# Debug.net
KiCad netlist of a schematic drawn in Altium Designer
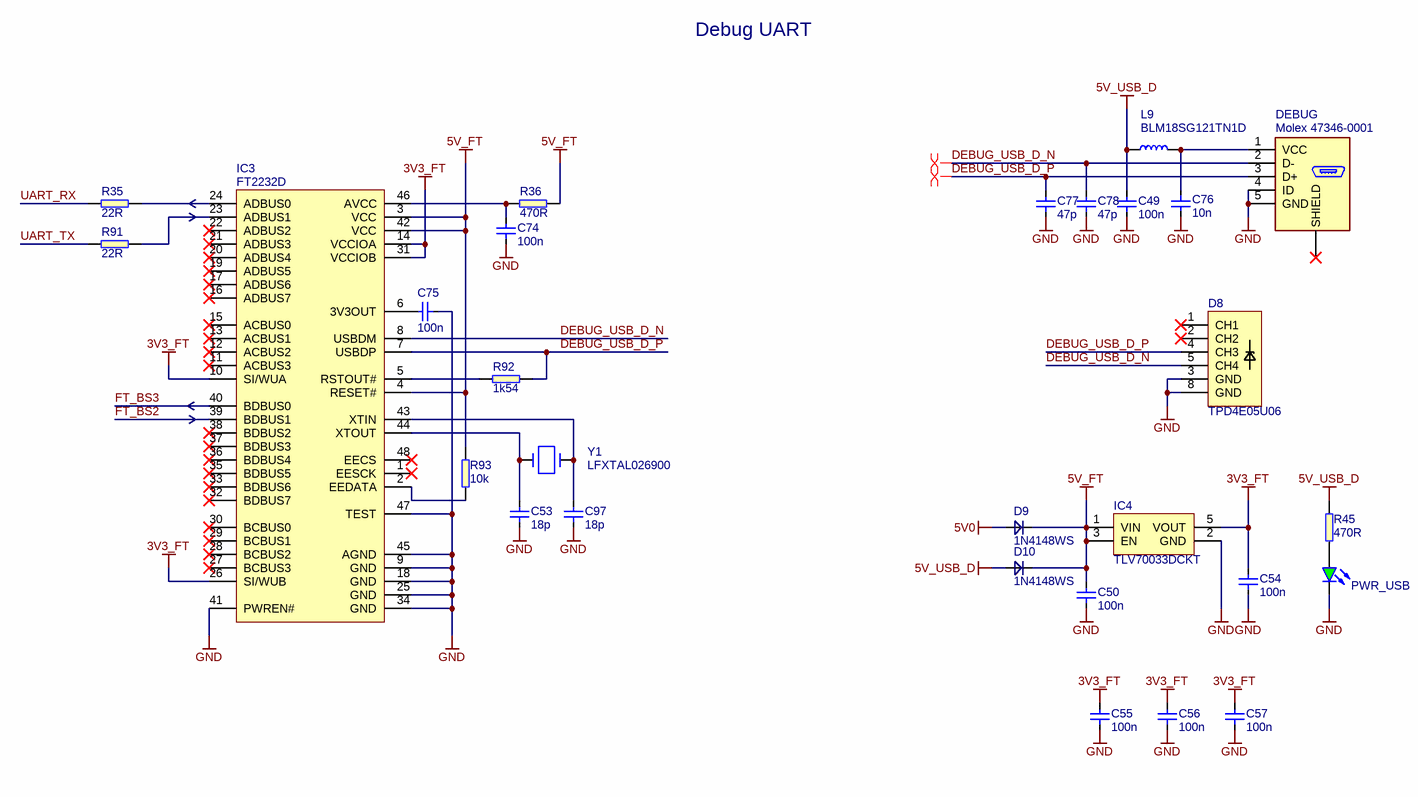
[diagram p0: Debug.SchDoc]

(export (version "E")
  (design (tool "Eeschema 10.0.6"))
  (components
    (comp (ref "C49")
      (value "100n")
      (footprint "0603")
      (description "MLCC SMT Capacitor 100nF 0603")
      (fields (field (name "PART NUMBER") "C_100n_0603") (field (name "MANUFACTURER") "WALSIN"))
      (libsource (lib "US-Plus-CPM") (part "C"))
    )
    (comp (ref "C50")
      (value "100n")
      (footprint "0402")
      (description "MLCC SMT Capacitor 100nF 0402")
      (fields (field (name "PART NUMBER") "C_100n_0402") (field (name "MANUFACTURER") "MULTICOMP"))
      (libsource (lib "US-Plus-CPM") (part "C"))
    )
    (comp (ref "C53")
      (value "18p")
      (footprint "0402")
      (description "MLCC SMT Capacitor 18pF 0603")
      (fields (field (name "PART NUMBER") "C_18p_0402") (field (name "MANUFACTURER") "KEMET"))
      (libsource (lib "US-Plus-CPM") (part "C"))
    )
    (comp (ref "C54")
      (value "100n")
      (footprint "0402")
      (description "MLCC SMT Capacitor 100nF 0402")
      (fields (field (name "PART NUMBER") "C_100n_0402") (field (name "MANUFACTURER") "MULTICOMP"))
      (libsource (lib "US-Plus-CPM") (part "C"))
    )
    (comp (ref "C55")
      (value "100n")
      (footprint "0402")
      (description "MLCC SMT Capacitor 100nF 0402")
      (fields (field (name "PART NUMBER") "C_100n_0402") (field (name "MANUFACTURER") "MULTICOMP"))
      (libsource (lib "US-Plus-CPM") (part "C"))
    )
    (comp (ref "C56")
      (value "100n")
      (footprint "0402")
      (description "MLCC SMT Capacitor 100nF 0402")
      (fields (field (name "PART NUMBER") "C_100n_0402") (field (name "MANUFACTURER") "MULTICOMP"))
      (libsource (lib "US-Plus-CPM") (part "C"))
    )
    (comp (ref "C57")
      (value "100n")
      (footprint "0402")
      (description "MLCC SMT Capacitor 100nF 0402")
      (fields (field (name "PART NUMBER") "C_100n_0402") (field (name "MANUFACTURER") "MULTICOMP"))
      (libsource (lib "US-Plus-CPM") (part "C"))
    )
    (comp (ref "C74")
      (value "100n")
      (footprint "0402")
      (description "MLCC SMT Capacitor 100nF 0402")
      (fields (field (name "PART NUMBER") "C_100n_0402") (field (name "MANUFACTURER") "MULTICOMP"))
      (libsource (lib "US-Plus-CPM") (part "C"))
    )
    (comp (ref "C75")
      (value "100n")
      (footprint "0402")
      (description "MLCC SMT Capacitor 100nF 0402")
      (fields (field (name "PART NUMBER") "C_100n_0402") (field (name "MANUFACTURER") "MULTICOMP"))
      (libsource (lib "US-Plus-CPM") (part "C"))
    )
    (comp (ref "C76")
      (value "10n")
      (footprint "0603")
      (description "MLCC SMT Capacitor 10nF 0603")
      (fields (field (name "PART NUMBER") "C_10n_0603") (field (name "MANUFACTURER") "AVX"))
      (libsource (lib "US-Plus-CPM") (part "C"))
    )
    (comp (ref "C77")
      (value "47p")
      (footprint "0402")
      (description "MLCC SMT Capacitor 47pF 0402")
      (fields (field (name "PART NUMBER") "C_47p_0402") (field (name "MANUFACTURER") "KEMET"))
      (libsource (lib "US-Plus-CPM") (part "C"))
    )
    (comp (ref "C78")
      (value "47p")
      (footprint "0402")
      (description "MLCC SMT Capacitor 47pF 0402")
      (fields (field (name "PART NUMBER") "C_47p_0402") (field (name "MANUFACTURER") "KEMET"))
      (libsource (lib "US-Plus-CPM") (part "C"))
    )
    (comp (ref "C97")
      (value "18p")
      (footprint "0402")
      (description "MLCC SMT Capacitor 18pF 0603")
      (fields (field (name "PART NUMBER") "C_18p_0402") (field (name "MANUFACTURER") "KEMET"))
      (libsource (lib "US-Plus-CPM") (part "C"))
    )
    (comp (ref "D8")
      (value "TPD4E05U06")
      (footprint "TPD4E05U06_PASS")
      (description "ESD Suppressors 4-CH")
      (fields
        (field (name "PART NUMBER") "TPD4E05U06_PASS")
        (field (name "MANUFACTURER") "Texas Instruments")
      )
      (libsource (lib "US-Plus-CPM") (part "TPD4E05U06"))
    )
    (comp (ref "D9")
      (value "1N4148WS")
      (footprint "SOD-323")
      (description "Diode small signal")
      (fields (field (name "MANUFACTURER") "MULTICOMP"))
      (libsource (lib "US-Plus-CPM") (part "diode"))
    )
    (comp (ref "D10")
      (value "1N4148WS")
      (footprint "SOD-323")
      (description "Diode small signal")
      (fields (field (name "MANUFACTURER") "MULTICOMP"))
      (libsource (lib "US-Plus-CPM") (part "diode"))
    )
    (comp (ref "DEBUG")
      (value "Molex 47346-0001")
      (footprint "CON-Molex-047346-0001")
      (description "USB - micro B Receptacle Connector 5 Position Surface Mount, Right Angle, Horizontal")
      (fields (field (name "PART NUMBER") "CON-Molex-47346-0001") (field (name "MANUFACTURER") "Molex"))
      (libsource (lib "US-Plus-CPM") (part "Micro USB B"))
    )
    (comp (ref "IC3")
      (value "FT2232D")
      (footprint "LQFP-48")
      (description "Dual USB-UART/FIFO")
      (fields (field (name "MANUFACTURER") "FTDI") (field (name "MPN") "FT2232D-REEL"))
      (libsource (lib "US-Plus-CPM") (part "FT2232"))
    )
    (comp (ref "IC4")
      (value "TLV70033DCKT")
      (footprint "SC70-5")
      (description "Voltage Regulator, 2V to 5.5V, 175mV Dropout, 3.3Vout, 200mAout")
      (fields (field (name "MANUFACTURER") "TEXAS INSTRUMENTS"))
      (libsource (lib "US-Plus-CPM") (part "TLV700"))
    )
    (comp (ref "L9")
      (value "BLM18SG121TN1D")
      (footprint "0603")
      (description "FERRITE BEAD, 0.025OHM, 3A, 0603")
      (fields (field (name "MANUFACTURER") "MURATA"))
      (libsource (lib "US-Plus-CPM") (part "Inductor SMT"))
    )
    (comp (ref "PWR_USB")
      (value "KPT-1608SGC")
      (footprint "LED0603")
      (description "LED Green 0603 case")
      (fields (field (name "PART NUMBER") "LED_G") (field (name "MANUFACTURER") "KINGBRIGHT"))
      (libsource (lib "US-Plus-CPM") (part "LED"))
    )
    (comp (ref "R35")
      (value "22R")
      (footprint "0402")
      (description "SMT Resistor 22R 0402")
      (fields (field (name "PART NUMBER") "R_22R_0402") (field (name "MANUFACTURER") "VISHAY"))
      (libsource (lib "") (part "R_1"))
    )
    (comp (ref "R36")
      (value "470R")
      (footprint "0402")
      (description "SMT Resistor 470R 0402")
      (fields (field (name "PART NUMBER") "R_470R_0402") (field (name "MANUFACTURER") "VISHAY"))
      (libsource (lib "US-Plus-CPM") (part "R"))
    )
    (comp (ref "R45")
      (value "470R")
      (footprint "0603")
      (description "SMT Resistor 470R 0603")
      (fields (field (name "PART NUMBER") "R_470R_0603") (field (name "MANUFACTURER") "BOURNS"))
      (libsource (lib "") (part "R_2"))
    )
    (comp (ref "R91")
      (value "22R")
      (footprint "0402")
      (description "SMT Resistor 22R 0402")
      (fields (field (name "PART NUMBER") "R_22R_0402") (field (name "MANUFACTURER") "VISHAY"))
      (libsource (lib "") (part "R_1"))
    )
    (comp (ref "R92")
      (value "1k54")
      (footprint "0402")
      (description "SMT Resistor 1k54 0402")
      (fields (field (name "PART NUMBER") "R_1k54_0402") (field (name "MANUFACTURER") "VISHAY"))
      (libsource (lib "US-Plus-CPM") (part "R"))
    )
    (comp (ref "R93")
      (value "10k")
      (footprint "0402")
      (description "SMT Resistor 0402")
      (fields (field (name "PART NUMBER") "R_10k_0402") (field (name "MANUFACTURER") "MULTICOMP"))
      (libsource (lib "") (part "R_1"))
    )
    (comp (ref "Y1")
      (value "LFXTAL026900")
      (footprint "crystal_smd")
      (description "CRYSTAL, 6MHZ, 18PF, SMD")
      (fields
        (field (name "PART NUMBER") "CRYSTAL_6MHz_SMD")
        (field (name "MANUFACTURER") "IQD FREQUENCY PRODUCTS")
      )
      (libsource (lib "US-Plus-CPM") (part "CRYSTAL"))
    )
  )
  (nets
    (net (code "1") (name "/DEBUG_USB_D_N") (class "Default")
      (node (ref "C78") (pin "2") (pinfunction "2_2") (pintype "passive"))
      (node (ref "D8") (pin "5") (pinfunction "CH4_5") (pintype "passive"))
      (node (ref "DEBUG") (pin "2") (pinfunction "D-_2") (pintype "passive"))
      (node (ref "IC3") (pin "8") (pinfunction "USBDM_8") (pintype "passive"))
    )
    (net (code "2") (name "/DEBUG_USB_D_P") (class "Default")
      (node (ref "C77") (pin "2") (pinfunction "2_2") (pintype "passive"))
      (node (ref "D8") (pin "4") (pinfunction "CH3_4") (pintype "passive"))
      (node (ref "DEBUG") (pin "3") (pinfunction "D+_3") (pintype "passive"))
      (node (ref "IC3") (pin "7") (pinfunction "USBDP_7") (pintype "passive"))
      (node (ref "R92") (pin "1") (pintype "passive"))
    )
    (net (code "3") (name "/FT_BS2") (class "Default")
      (node (ref "IC3") (pin "39") (pinfunction "BDBUS1_39") (pintype "passive"))
    )
    (net (code "4") (name "/FT_BS3") (class "Default")
      (node (ref "IC3") (pin "40") (pinfunction "BDBUS0_40") (pintype "passive"))
    )
    (net (code "5") (name "/UART_RX") (class "Default") (node (ref "R35") (pin "1") (pintype "passive")))
    (net (code "6") (name "/UART_TX") (class "Default") (node (ref "R91") (pin "1") (pintype "passive")))
    (net (code "7") (name "3V3_FT") (class "Default")
      (node (ref "C54") (pin "2") (pinfunction "2_2") (pintype "passive"))
      (node (ref "C55") (pin "2") (pinfunction "2_2") (pintype "passive"))
      (node (ref "C56") (pin "2") (pinfunction "2_2") (pintype "passive"))
      (node (ref "C57") (pin "2") (pinfunction "2_2") (pintype "passive"))
      (node (ref "IC3") (pin "10") (pinfunction "SI/WUA_10") (pintype "passive"))
      (node (ref "IC3") (pin "14") (pinfunction "VCCIOA_14") (pintype "passive"))
      (node (ref "IC3") (pin "26") (pinfunction "SI/WUB_26") (pintype "passive"))
      (node (ref "IC3") (pin "31") (pinfunction "VCCIOB_31") (pintype "passive"))
      (node (ref "IC4") (pin "5") (pinfunction "VOUT_5") (pintype "passive"))
    )
    (net (code "8") (name "5V0") (class "Default")
      (node (ref "D9") (pin "A") (pinfunction "A_A") (pintype "passive"))
    )
    (net (code "9") (name "5V_FT") (class "Default")
      (node (ref "C50") (pin "2") (pinfunction "2_2") (pintype "passive"))
      (node (ref "D10") (pin "C") (pinfunction "C_C") (pintype "passive"))
      (node (ref "D9") (pin "C") (pinfunction "C_C") (pintype "passive"))
      (node (ref "IC3") (pin "3") (pinfunction "VCC_3") (pintype "passive"))
      (node (ref "IC3") (pin "4") (pinfunction "RESET#_4") (pintype "passive"))
      (node (ref "IC3") (pin "42") (pinfunction "VCC_42") (pintype "passive"))
      (node (ref "IC4") (pin "1") (pinfunction "VIN_1") (pintype "passive"))
      (node (ref "IC4") (pin "3") (pinfunction "EN_3") (pintype "passive"))
      (node (ref "R36") (pin "1") (pintype "passive"))
      (node (ref "R93") (pin "2") (pintype "passive"))
    )
    (net (code "10") (name "5V_USB_D") (class "Default")
      (node (ref "C49") (pin "2") (pinfunction "2_2") (pintype "passive"))
      (node (ref "D10") (pin "A") (pinfunction "A_A") (pintype "passive"))
      (node (ref "L9") (pin "1") (pintype "passive"))
      (node (ref "R45") (pin "2") (pintype "passive"))
    )
    (net (code "11") (name "GND") (class "Default")
      (node (ref "C49") (pin "1") (pinfunction "1_1") (pintype "passive"))
      (node (ref "C50") (pin "1") (pinfunction "1_1") (pintype "passive"))
      (node (ref "C53") (pin "1") (pinfunction "1_1") (pintype "passive"))
      (node (ref "C54") (pin "1") (pinfunction "1_1") (pintype "passive"))
      (node (ref "C55") (pin "1") (pinfunction "1_1") (pintype "passive"))
      (node (ref "C56") (pin "1") (pinfunction "1_1") (pintype "passive"))
      (node (ref "C57") (pin "1") (pinfunction "1_1") (pintype "passive"))
      (node (ref "C74") (pin "1") (pinfunction "1_1") (pintype "passive"))
      (node (ref "C75") (pin "1") (pinfunction "1_1") (pintype "passive"))
      (node (ref "C76") (pin "2") (pinfunction "2_2") (pintype "passive"))
      (node (ref "C77") (pin "1") (pinfunction "1_1") (pintype "passive"))
      (node (ref "C78") (pin "1") (pinfunction "1_1") (pintype "passive"))
      (node (ref "C97") (pin "1") (pinfunction "1_1") (pintype "passive"))
      (node (ref "D8") (pin "3") (pinfunction "GND_3") (pintype "passive"))
      (node (ref "D8") (pin "8") (pinfunction "GND_8") (pintype "passive"))
      (node (ref "DEBUG") (pin "4") (pinfunction "ID_4") (pintype "passive"))
      (node (ref "DEBUG") (pin "5") (pinfunction "GND_5") (pintype "power_in"))
      (node (ref "IC3") (pin "18") (pinfunction "GND_18") (pintype "passive"))
      (node (ref "IC3") (pin "25") (pinfunction "GND_25") (pintype "passive"))
      (node (ref "IC3") (pin "34") (pinfunction "GND_34") (pintype "passive"))
      (node (ref "IC3") (pin "41") (pinfunction "PWREN#_41") (pintype "passive"))
      (node (ref "IC3") (pin "45") (pinfunction "AGND_45") (pintype "passive"))
      (node (ref "IC3") (pin "47") (pinfunction "TEST_47") (pintype "passive"))
      (node (ref "IC3") (pin "9") (pinfunction "GND_9") (pintype "passive"))
      (node (ref "IC4") (pin "2") (pinfunction "GND_2") (pintype "passive"))
      (node (ref "PWR_USB") (pin "K") (pinfunction "K_K") (pintype "passive"))
    )
    (net (code "12") (name "Net-(DEBUG-VCC)") (class "Default")
      (node (ref "C76") (pin "1") (pinfunction "1_1") (pintype "passive"))
      (node (ref "DEBUG") (pin "1") (pinfunction "VCC_1") (pintype "power_in"))
      (node (ref "L9") (pin "2") (pintype "passive"))
    )
    (net (code "13") (name "Net-(IC3-3V3OUT)") (class "Default")
      (node (ref "C75") (pin "2") (pinfunction "2_2") (pintype "passive"))
      (node (ref "IC3") (pin "6") (pinfunction "3V3OUT_6") (pintype "passive"))
    )
    (net (code "14") (name "Net-(IC3-ADBUS0)") (class "Default")
      (node (ref "IC3") (pin "24") (pinfunction "ADBUS0_24") (pintype "passive"))
      (node (ref "R35") (pin "2") (pintype "passive"))
    )
    (net (code "15") (name "Net-(IC3-ADBUS1)") (class "Default")
      (node (ref "IC3") (pin "23") (pinfunction "ADBUS1_23") (pintype "passive"))
      (node (ref "R91") (pin "2") (pintype "passive"))
    )
    (net (code "16") (name "Net-(IC3-AVCC)") (class "Default")
      (node (ref "C74") (pin "2") (pinfunction "2_2") (pintype "passive"))
      (node (ref "IC3") (pin "46") (pinfunction "AVCC_46") (pintype "passive"))
      (node (ref "R36") (pin "2") (pintype "passive"))
    )
    (net (code "17") (name "Net-(IC3-EEDATA)") (class "Default")
      (node (ref "IC3") (pin "2") (pinfunction "EEDATA_2") (pintype "passive"))
      (node (ref "R93") (pin "1") (pintype "passive"))
    )
    (net (code "18") (name "Net-(IC3-RSTOUT#)") (class "Default")
      (node (ref "IC3") (pin "5") (pinfunction "RSTOUT#_5") (pintype "passive"))
      (node (ref "R92") (pin "2") (pintype "passive"))
    )
    (net (code "19") (name "Net-(IC3-XTIN)") (class "Default")
      (node (ref "C97") (pin "2") (pinfunction "2_2") (pintype "passive"))
      (node (ref "IC3") (pin "43") (pinfunction "XTIN_43") (pintype "passive"))
      (node (ref "Y1") (pin "1") (pinfunction "1_1") (pintype "passive"))
    )
    (net (code "20") (name "Net-(IC3-XTOUT)") (class "Default")
      (node (ref "C53") (pin "2") (pinfunction "2_2") (pintype "passive"))
      (node (ref "IC3") (pin "44") (pinfunction "XTOUT_44") (pintype "passive"))
      (node (ref "Y1") (pin "2") (pinfunction "2_2") (pintype "passive"))
    )
    (net (code "21") (name "Net-(PWR_USB-PadA)") (class "Default")
      (node (ref "PWR_USB") (pin "A") (pinfunction "A_A") (pintype "passive"))
      (node (ref "R45") (pin "1") (pintype "passive"))
    )
    (net (code "22") (name "unconnected-(D8-CH1-Pad1)") (class "Default")
      (node (ref "D8") (pin "1") (pinfunction "CH1_1") (pintype "passive+no_connect"))
    )
    (net (code "23") (name "unconnected-(D8-CH2-Pad2)") (class "Default")
      (node (ref "D8") (pin "2") (pinfunction "CH2_2") (pintype "passive+no_connect"))
    )
    (net (code "24") (name "unconnected-(DEBUG-SHIELD-PadS)") (class "Default")
      (node (ref "DEBUG") (pin "S") (pinfunction "SHIELD_S") (pintype "passive+no_connect"))
    )
    (net (code "25") (name "unconnected-(IC3-ACBUS0-Pad15)") (class "Default")
      (node (ref "IC3") (pin "15") (pinfunction "ACBUS0_15") (pintype "passive+no_connect"))
    )
    (net (code "26") (name "unconnected-(IC3-ACBUS1-Pad13)") (class "Default")
      (node (ref "IC3") (pin "13") (pinfunction "ACBUS1_13") (pintype "passive+no_connect"))
    )
    (net (code "27") (name "unconnected-(IC3-ACBUS2-Pad12)") (class "Default")
      (node (ref "IC3") (pin "12") (pinfunction "ACBUS2_12") (pintype "passive+no_connect"))
    )
    (net (code "28") (name "unconnected-(IC3-ACBUS3-Pad11)") (class "Default")
      (node (ref "IC3") (pin "11") (pinfunction "ACBUS3_11") (pintype "passive+no_connect"))
    )
    (net (code "29") (name "unconnected-(IC3-ADBUS2-Pad22)") (class "Default")
      (node (ref "IC3") (pin "22") (pinfunction "ADBUS2_22") (pintype "passive+no_connect"))
    )
    (net (code "30") (name "unconnected-(IC3-ADBUS3-Pad21)") (class "Default")
      (node (ref "IC3") (pin "21") (pinfunction "ADBUS3_21") (pintype "passive+no_connect"))
    )
    (net (code "31") (name "unconnected-(IC3-ADBUS4-Pad20)") (class "Default")
      (node (ref "IC3") (pin "20") (pinfunction "ADBUS4_20") (pintype "passive+no_connect"))
    )
    (net (code "32") (name "unconnected-(IC3-ADBUS5-Pad19)") (class "Default")
      (node (ref "IC3") (pin "19") (pinfunction "ADBUS5_19") (pintype "passive+no_connect"))
    )
    (net (code "33") (name "unconnected-(IC3-ADBUS6-Pad17)") (class "Default")
      (node (ref "IC3") (pin "17") (pinfunction "ADBUS6_17") (pintype "passive+no_connect"))
    )
    (net (code "34") (name "unconnected-(IC3-ADBUS7-Pad16)") (class "Default")
      (node (ref "IC3") (pin "16") (pinfunction "ADBUS7_16") (pintype "passive+no_connect"))
    )
    (net (code "35") (name "unconnected-(IC3-BCBUS0-Pad30)") (class "Default")
      (node (ref "IC3") (pin "30") (pinfunction "BCBUS0_30") (pintype "passive+no_connect"))
    )
    (net (code "36") (name "unconnected-(IC3-BCBUS1-Pad29)") (class "Default")
      (node (ref "IC3") (pin "29") (pinfunction "BCBUS1_29") (pintype "passive+no_connect"))
    )
    (net (code "37") (name "unconnected-(IC3-BCBUS2-Pad28)") (class "Default")
      (node (ref "IC3") (pin "28") (pinfunction "BCBUS2_28") (pintype "passive+no_connect"))
    )
    (net (code "38") (name "unconnected-(IC3-BCBUS3-Pad27)") (class "Default")
      (node (ref "IC3") (pin "27") (pinfunction "BCBUS3_27") (pintype "passive+no_connect"))
    )
    (net (code "39") (name "unconnected-(IC3-BDBUS2-Pad38)") (class "Default")
      (node (ref "IC3") (pin "38") (pinfunction "BDBUS2_38") (pintype "passive+no_connect"))
    )
    (net (code "40") (name "unconnected-(IC3-BDBUS3-Pad37)") (class "Default")
      (node (ref "IC3") (pin "37") (pinfunction "BDBUS3_37") (pintype "passive+no_connect"))
    )
    (net (code "41") (name "unconnected-(IC3-BDBUS4-Pad36)") (class "Default")
      (node (ref "IC3") (pin "36") (pinfunction "BDBUS4_36") (pintype "passive+no_connect"))
    )
    (net (code "42") (name "unconnected-(IC3-BDBUS5-Pad35)") (class "Default")
      (node (ref "IC3") (pin "35") (pinfunction "BDBUS5_35") (pintype "passive+no_connect"))
    )
    (net (code "43") (name "unconnected-(IC3-BDBUS6-Pad33)") (class "Default")
      (node (ref "IC3") (pin "33") (pinfunction "BDBUS6_33") (pintype "passive+no_connect"))
    )
    (net (code "44") (name "unconnected-(IC3-BDBUS7-Pad32)") (class "Default")
      (node (ref "IC3") (pin "32") (pinfunction "BDBUS7_32") (pintype "passive+no_connect"))
    )
    (net (code "45") (name "unconnected-(IC3-EECS-Pad48)") (class "Default")
      (node (ref "IC3") (pin "48") (pinfunction "EECS_48") (pintype "passive+no_connect"))
    )
    (net (code "46") (name "unconnected-(IC3-EESCK-Pad1)") (class "Default")
      (node (ref "IC3") (pin "1") (pinfunction "EESCK_1") (pintype "passive+no_connect"))
    )
  )
)
